# gL_control_PCB.net
KiCad netlist of a schematic drawn in EAGLE
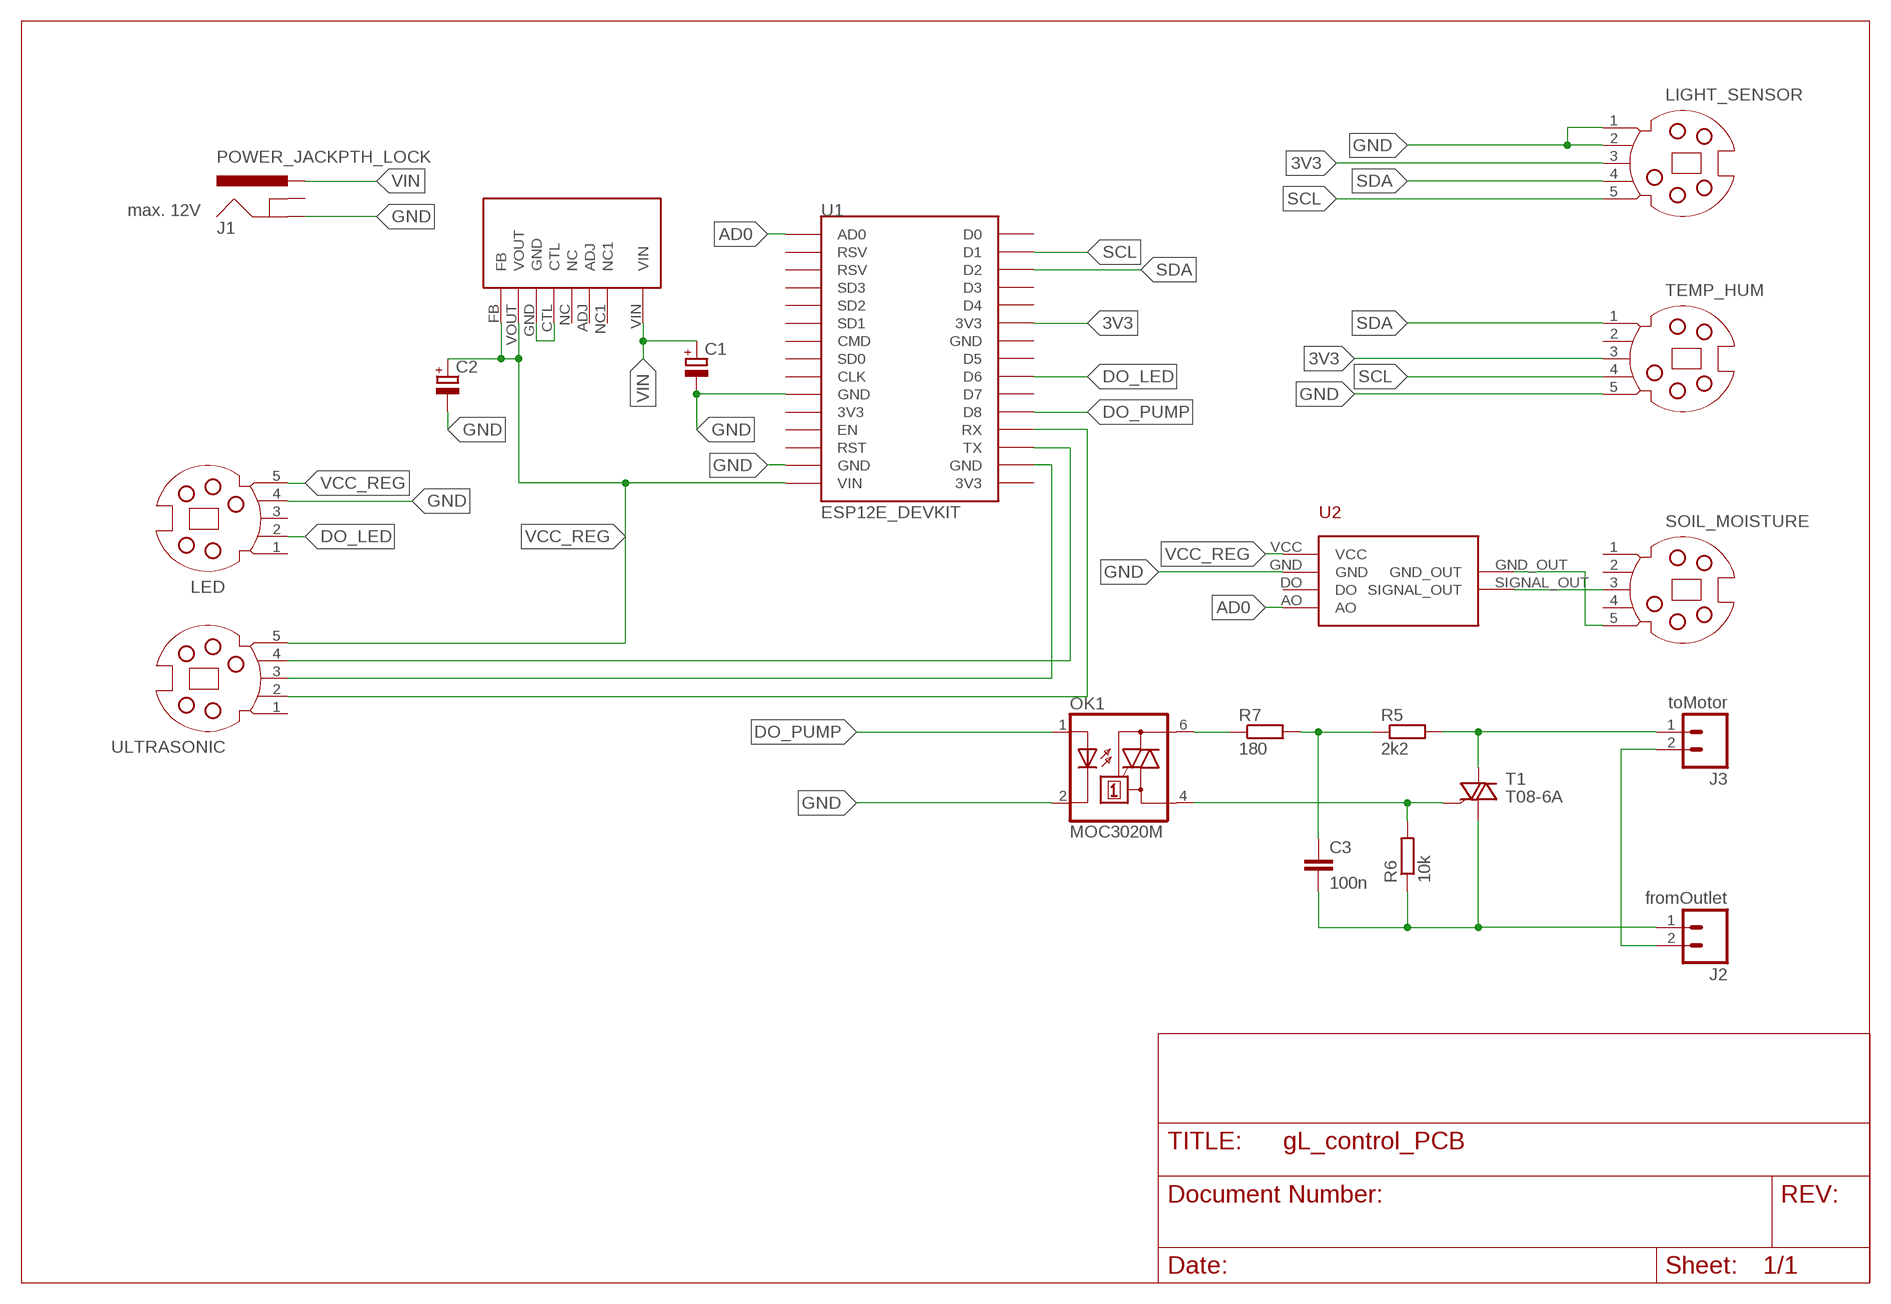
[diagram p0: schematic, sheet 1]

(export (version "E")
  (design (tool "Eeschema 10.0.6"))
  (components
    (comp (ref "C1")
      (value "CPOL-EUE2.5-5")
      (footprint "eagle-import:E2,5-5")
      (libsource (lib "eagle-import") (part "CPOL-EUE2.5-5"))
    )
    (comp (ref "C2")
      (value "CPOL-EUE5-8.5")
      (footprint "eagle-import:E5-8,5")
      (libsource (lib "eagle-import") (part "CPOL-EUE5-8.5"))
    )
    (comp (ref "C3")
      (value "100n")
      (footprint "eagle-import:C7.5B5")
      (libsource (lib "eagle-import") (part "C7.5/5"))
    )
    (comp (ref "J1")
      (value "POWER_JACKPTH_LOCK")
      (footprint "eagle-import:POWER_JACK_PTH_LOCK")
      (libsource (lib "eagle-import") (part "POWER_JACKPTH_LOCK"))
    )
    (comp (ref "J2")
      (value "fromOutlet")
      (footprint "eagle-import:SCREWTERMINAL-5MM-2")
      (libsource (lib "eagle-import") (part "M025MM"))
    )
    (comp (ref "J3")
      (value "toMotor")
      (footprint "eagle-import:SCREWTERMINAL-5MM-2")
      (libsource (lib "eagle-import") (part "M025MM"))
    )
    (comp (ref "LED")
      (value "MD05SS")
      (footprint "eagle-import:MDIN05SS")
      (libsource (lib "eagle-import") (part "MD05SS"))
    )
    (comp (ref "LIGHT_SENSOR")
      (value "MD05SS")
      (footprint "eagle-import:MDIN05SS")
      (libsource (lib "eagle-import") (part "MD05SS"))
    )
    (comp (ref "OK1")
      (value "MOC3020M")
      (footprint "eagle-import:DIL06")
      (fields (field (name "MF") "FAIRCHILD SEMICONDUCTOR") (field (name "MPN") "MOC3020-M"))
      (libsource (lib "eagle-import") (part "MOC30M20"))
    )
    (comp (ref "R5")
      (value "2k2")
      (footprint "eagle-import:0309_10")
      (libsource (lib "eagle-import") (part "R-EU_0309/10"))
    )
    (comp (ref "R6")
      (value "10k")
      (footprint "eagle-import:0309_10")
      (libsource (lib "eagle-import") (part "R-EU_0309/10"))
    )
    (comp (ref "R7")
      (value "180")
      (footprint "eagle-import:0309_10")
      (libsource (lib "eagle-import") (part "R-EU_0309/10"))
    )
    (comp (ref "SOIL_MOISTURE")
      (value "MD05SS")
      (footprint "eagle-import:MDIN05SS")
      (libsource (lib "eagle-import") (part "MD05SS"))
    )
    (comp (ref "T1")
      (value "T08-6A")
      (footprint "eagle-import:TO92-3")
      (libsource (lib "eagle-import") (part "T08-6A"))
    )
    (comp (ref "TEMP_HUM")
      (value "MD05SS")
      (footprint "eagle-import:MDIN05SS")
      (libsource (lib "eagle-import") (part "MD05SS"))
    )
    (comp (ref "U$1")
      (value "BH5220A")
      (footprint "eagle-import:BH5220A")
      (libsource (lib "eagle-import") (part "BH5220A"))
    )
    (comp (ref "U1")
      (value "ESP12E_DEVKIT")
      (footprint "eagle-import:ESP12E_DEVKIT")
      (libsource (lib "eagle-import") (part "ESP12E_DEVKIT"))
    )
    (comp (ref "U2")
      (value "LM393_SOIL_MOISTURE")
      (footprint "eagle-import:LM393_SOIL_SENSOR")
      (libsource (lib "eagle-import") (part "LM393_SOIL_MOISTURE"))
    )
    (comp (ref "ULTRASONIC")
      (value "MD05SS")
      (footprint "eagle-import:MDIN05SS")
      (libsource (lib "eagle-import") (part "MD05SS"))
    )
  )
  (nets
    (net (code "1") (name "3V3") (class "Default")
      (node (ref "LIGHT_SENSOR") (pin "3") (pinfunction "3_3") (pintype "passive"))
      (node (ref "TEMP_HUM") (pin "3") (pinfunction "3_3") (pintype "passive"))
      (node (ref "U1") (pin "3V3@1") (pinfunction "3V3_3V3@1") (pintype "bidirectional"))
    )
    (net (code "2") (name "AD0") (class "Default")
      (node (ref "U1") (pin "AD0") (pinfunction "AD0_AD0") (pintype "bidirectional"))
      (node (ref "U2") (pin "AO") (pinfunction "AO_AO") (pintype "bidirectional"))
    )
    (net (code "3") (name "DO_LED") (class "Default")
      (node (ref "LED") (pin "2") (pinfunction "2_2") (pintype "passive"))
      (node (ref "U1") (pin "D6") (pinfunction "D6_D6") (pintype "bidirectional"))
    )
    (net (code "4") (name "DO_PUMP") (class "Default")
      (node (ref "OK1") (pin "1") (pinfunction "A_1") (pintype "passive"))
      (node (ref "U1") (pin "D8") (pinfunction "D8_D8") (pintype "bidirectional"))
    )
    (net (code "5") (name "GND") (class "Default")
      (node (ref "C1") (pin "-") (pinfunction "-_-") (pintype "passive"))
      (node (ref "C2") (pin "-") (pinfunction "-_-") (pintype "passive"))
      (node (ref "J1") (pin "GND") (pinfunction "GND_GND") (pintype "bidirectional"))
      (node (ref "LED") (pin "4") (pinfunction "4_4") (pintype "passive"))
      (node (ref "LIGHT_SENSOR") (pin "1") (pinfunction "1_1") (pintype "passive"))
      (node (ref "LIGHT_SENSOR") (pin "2") (pinfunction "2_2") (pintype "passive"))
      (node (ref "OK1") (pin "2") (pinfunction "C_2") (pintype "passive"))
      (node (ref "TEMP_HUM") (pin "5") (pinfunction "5_5") (pintype "passive"))
      (node (ref "U1") (pin "GND@0") (pinfunction "GND_GND@0") (pintype "bidirectional"))
      (node (ref "U1") (pin "GND@1") (pinfunction "GND_GND@1") (pintype "bidirectional"))
      (node (ref "U2") (pin "GND") (pinfunction "GND_GND") (pintype "bidirectional"))
    )
    (net (code "6") (name "Net-(C3-Pad1)") (class "Default")
      (node (ref "C3") (pin "1") (pinfunction "1_1") (pintype "passive"))
      (node (ref "R5") (pin "1") (pinfunction "1_1") (pintype "passive"))
      (node (ref "R7") (pin "2") (pinfunction "2_2") (pintype "passive"))
    )
    (net (code "7") (name "Net-(J2-Pad2)") (class "Default")
      (node (ref "J2") (pin "2") (pinfunction "2_2") (pintype "passive"))
      (node (ref "J3") (pin "2") (pinfunction "2_2") (pintype "passive"))
    )
    (net (code "8") (name "Net-(OK1-A1)") (class "Default")
      (node (ref "OK1") (pin "4") (pinfunction "A1_4") (pintype "passive"))
      (node (ref "R6") (pin "2") (pinfunction "2_2") (pintype "passive"))
      (node (ref "T1") (pin "G") (pinfunction "G_G") (pintype "passive"))
    )
    (net (code "9") (name "Net-(OK1-A2)") (class "Default")
      (node (ref "OK1") (pin "6") (pinfunction "A2_6") (pintype "passive"))
      (node (ref "R7") (pin "1") (pinfunction "1_1") (pintype "passive"))
    )
    (net (code "10") (name "Net-(SOIL_MOISTURE-Pad3)") (class "Default")
      (node (ref "SOIL_MOISTURE") (pin "3") (pinfunction "3_3") (pintype "passive"))
      (node (ref "U2") (pin "SIGNAL_OUT") (pinfunction "SIGNAL_OUT_SIGNAL_OUT") (pintype "bidirectional"))
    )
    (net (code "11") (name "Net-(SOIL_MOISTURE-Pad5)") (class "Default")
      (node (ref "SOIL_MOISTURE") (pin "5") (pinfunction "5_5") (pintype "passive"))
      (node (ref "U2") (pin "GND_OUT") (pinfunction "GND_OUT_GND_OUT") (pintype "bidirectional"))
    )
    (net (code "12") (name "Net-(T1-A1)") (class "Default")
      (node (ref "C3") (pin "2") (pinfunction "2_2") (pintype "passive"))
      (node (ref "J2") (pin "1") (pinfunction "1_1") (pintype "passive"))
      (node (ref "R6") (pin "1") (pinfunction "1_1") (pintype "passive"))
      (node (ref "T1") (pin "A2") (pinfunction "A1_A2") (pintype "passive"))
    )
    (net (code "13") (name "Net-(T1-A2)") (class "Default")
      (node (ref "J3") (pin "1") (pinfunction "1_1") (pintype "passive"))
      (node (ref "R5") (pin "2") (pinfunction "2_2") (pintype "passive"))
      (node (ref "T1") (pin "A1") (pinfunction "A2_A1") (pintype "passive"))
    )
    (net (code "14") (name "Net-(U$1-PadCTL)") (class "Default")
      (node (ref "U$1") (pin "CTL") (pinfunction "CTL_CTL") (pintype "bidirectional"))
      (node (ref "U$1") (pin "GND") (pinfunction "GND_GND") (pintype "bidirectional"))
    )
    (net (code "15") (name "Net-(U1-GND-PadGND@3)") (class "Default")
      (node (ref "U1") (pin "GND@3") (pinfunction "GND_GND@3") (pintype "bidirectional"))
      (node (ref "ULTRASONIC") (pin "3") (pinfunction "3_3") (pintype "passive"))
    )
    (net (code "16") (name "Net-(U1-PadRX)") (class "Default")
      (node (ref "U1") (pin "RX") (pinfunction "RX_RX") (pintype "bidirectional"))
      (node (ref "ULTRASONIC") (pin "2") (pinfunction "2_2") (pintype "passive"))
    )
    (net (code "17") (name "Net-(U1-PadTX)") (class "Default")
      (node (ref "U1") (pin "TX") (pinfunction "TX_TX") (pintype "bidirectional"))
      (node (ref "ULTRASONIC") (pin "4") (pinfunction "4_4") (pintype "passive"))
    )
    (net (code "18") (name "SCL") (class "Default")
      (node (ref "LIGHT_SENSOR") (pin "5") (pinfunction "5_5") (pintype "passive"))
      (node (ref "TEMP_HUM") (pin "4") (pinfunction "4_4") (pintype "passive"))
      (node (ref "U1") (pin "D1") (pinfunction "D1_D1") (pintype "bidirectional"))
    )
    (net (code "19") (name "SDA") (class "Default")
      (node (ref "LIGHT_SENSOR") (pin "4") (pinfunction "4_4") (pintype "passive"))
      (node (ref "TEMP_HUM") (pin "1") (pinfunction "1_1") (pintype "passive"))
      (node (ref "U1") (pin "D2") (pinfunction "D2_D2") (pintype "bidirectional"))
    )
    (net (code "20") (name "VCC_REG") (class "Default")
      (node (ref "C2") (pin "+") (pinfunction "+_+") (pintype "passive"))
      (node (ref "LED") (pin "5") (pinfunction "5_5") (pintype "passive"))
      (node (ref "U$1") (pin "FB") (pinfunction "FB_FB") (pintype "bidirectional"))
      (node (ref "U$1") (pin "VOUT") (pinfunction "VOUT_VOUT") (pintype "bidirectional"))
      (node (ref "U1") (pin "VIN") (pinfunction "VIN_VIN") (pintype "bidirectional"))
      (node (ref "U2") (pin "VCC") (pinfunction "VCC_VCC") (pintype "bidirectional"))
      (node (ref "ULTRASONIC") (pin "5") (pinfunction "5_5") (pintype "passive"))
    )
    (net (code "21") (name "VIN") (class "Default")
      (node (ref "C1") (pin "+") (pinfunction "+_+") (pintype "passive"))
      (node (ref "J1") (pin "PWR") (pinfunction "PWR_PWR") (pintype "bidirectional"))
      (node (ref "U$1") (pin "VIN") (pinfunction "VIN_VIN") (pintype "bidirectional"))
    )
    (net (code "22") (name "unconnected-(J1-PadGNDBREAK)") (class "Default")
      (node (ref "J1") (pin "GNDBREAK") (pinfunction "GNDBREAK_GNDBREAK") (pintype "bidirectional"))
    )
    (net (code "23") (name "unconnected-(LED-Pad1)") (class "Default")
      (node (ref "LED") (pin "1") (pinfunction "1_1") (pintype "passive"))
    )
    (net (code "24") (name "unconnected-(LED-Pad3)") (class "Default")
      (node (ref "LED") (pin "3") (pinfunction "3_3") (pintype "passive"))
    )
    (net (code "25") (name "unconnected-(SOIL_MOISTURE-Pad1)") (class "Default")
      (node (ref "SOIL_MOISTURE") (pin "1") (pinfunction "1_1") (pintype "passive"))
    )
    (net (code "26") (name "unconnected-(SOIL_MOISTURE-Pad2)") (class "Default")
      (node (ref "SOIL_MOISTURE") (pin "2") (pinfunction "2_2") (pintype "passive"))
    )
    (net (code "27") (name "unconnected-(SOIL_MOISTURE-Pad4)") (class "Default")
      (node (ref "SOIL_MOISTURE") (pin "4") (pinfunction "4_4") (pintype "passive"))
    )
    (net (code "28") (name "unconnected-(TEMP_HUM-Pad2)") (class "Default")
      (node (ref "TEMP_HUM") (pin "2") (pinfunction "2_2") (pintype "passive"))
    )
    (net (code "29") (name "unconnected-(U$1-PadADJ)") (class "Default")
      (node (ref "U$1") (pin "ADJ") (pinfunction "ADJ_ADJ") (pintype "bidirectional"))
    )
    (net (code "30") (name "unconnected-(U$1-PadNC)") (class "Default")
      (node (ref "U$1") (pin "NC") (pinfunction "NC_NC") (pintype "bidirectional"))
    )
    (net (code "31") (name "unconnected-(U$1-PadNC1)") (class "Default")
      (node (ref "U$1") (pin "NC1") (pinfunction "NC1_NC1") (pintype "bidirectional"))
    )
    (net (code "32") (name "unconnected-(U1-3V3-Pad3V3@0)") (class "Default")
      (node (ref "U1") (pin "3V3@0") (pinfunction "3V3_3V3@0") (pintype "bidirectional"))
    )
    (net (code "33") (name "unconnected-(U1-3V3-Pad3V3@2)") (class "Default")
      (node (ref "U1") (pin "3V3@2") (pinfunction "3V3_3V3@2") (pintype "bidirectional"))
    )
    (net (code "34") (name "unconnected-(U1-GND-PadGND@2)") (class "Default")
      (node (ref "U1") (pin "GND@2") (pinfunction "GND_GND@2") (pintype "bidirectional"))
    )
    (net (code "35") (name "unconnected-(U1-PadCLK)") (class "Default")
      (node (ref "U1") (pin "CLK") (pinfunction "CLK_CLK") (pintype "bidirectional"))
    )
    (net (code "36") (name "unconnected-(U1-PadCMD)") (class "Default")
      (node (ref "U1") (pin "CMD") (pinfunction "CMD_CMD") (pintype "bidirectional"))
    )
    (net (code "37") (name "unconnected-(U1-PadD0)") (class "Default")
      (node (ref "U1") (pin "D0") (pinfunction "D0_D0") (pintype "bidirectional"))
    )
    (net (code "38") (name "unconnected-(U1-PadD3)") (class "Default")
      (node (ref "U1") (pin "D3") (pinfunction "D3_D3") (pintype "bidirectional"))
    )
    (net (code "39") (name "unconnected-(U1-PadD4)") (class "Default")
      (node (ref "U1") (pin "D4") (pinfunction "D4_D4") (pintype "bidirectional"))
    )
    (net (code "40") (name "unconnected-(U1-PadD5)") (class "Default")
      (node (ref "U1") (pin "D5") (pinfunction "D5_D5") (pintype "bidirectional"))
    )
    (net (code "41") (name "unconnected-(U1-PadD7)") (class "Default")
      (node (ref "U1") (pin "D7") (pinfunction "D7_D7") (pintype "bidirectional"))
    )
    (net (code "42") (name "unconnected-(U1-PadEN)") (class "Default")
      (node (ref "U1") (pin "EN") (pinfunction "EN_EN") (pintype "bidirectional"))
    )
    (net (code "43") (name "unconnected-(U1-PadRST)") (class "Default")
      (node (ref "U1") (pin "RST") (pinfunction "RST_RST") (pintype "bidirectional"))
    )
    (net (code "44") (name "unconnected-(U1-PadSD0)") (class "Default")
      (node (ref "U1") (pin "SD0") (pinfunction "SD0_SD0") (pintype "bidirectional"))
    )
    (net (code "45") (name "unconnected-(U1-PadSD1)") (class "Default")
      (node (ref "U1") (pin "SD1") (pinfunction "SD1_SD1") (pintype "bidirectional"))
    )
    (net (code "46") (name "unconnected-(U1-PadSD2)") (class "Default")
      (node (ref "U1") (pin "SD2") (pinfunction "SD2_SD2") (pintype "bidirectional"))
    )
    (net (code "47") (name "unconnected-(U1-PadSD3)") (class "Default")
      (node (ref "U1") (pin "SD3") (pinfunction "SD3_SD3") (pintype "bidirectional"))
    )
    (net (code "48") (name "unconnected-(U1-RSV-PadRSV@0)") (class "Default")
      (node (ref "U1") (pin "RSV@0") (pinfunction "RSV_RSV@0") (pintype "bidirectional"))
    )
    (net (code "49") (name "unconnected-(U1-RSV-PadRSV@1)") (class "Default")
      (node (ref "U1") (pin "RSV@1") (pinfunction "RSV_RSV@1") (pintype "bidirectional"))
    )
    (net (code "50") (name "unconnected-(U2-PadDO)") (class "Default")
      (node (ref "U2") (pin "DO") (pinfunction "DO_DO") (pintype "bidirectional"))
    )
    (net (code "51") (name "unconnected-(ULTRASONIC-Pad1)") (class "Default")
      (node (ref "ULTRASONIC") (pin "1") (pinfunction "1_1") (pintype "passive"))
    )
  )
)
